# AS504XX_BreakoutV4.net
KiCad netlist of a schematic drawn in EAGLE
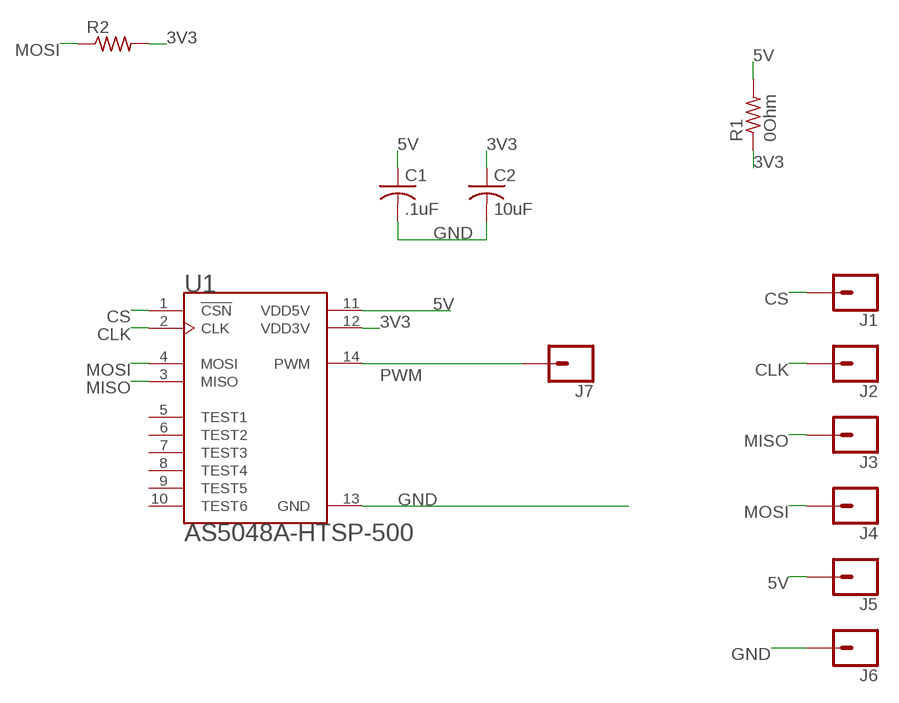
[diagram p0: schematic, sheet 1]

(export (version "E")
  (design (tool "Eeschema 10.0.6"))
  (components
    (comp (ref "C1")
      (value ".1uF")
      (footprint "eagle-import:C0402")
      (libsource (lib "eagle-import") (part "C-USC0402"))
    )
    (comp (ref "C2")
      (value "10uF")
      (footprint "eagle-import:C0402")
      (libsource (lib "eagle-import") (part "C-USC0402"))
    )
    (comp (ref "J1")
      (value "CONN_01")
      (footprint "eagle-import:1X01")
      (libsource (lib "eagle-import") (part "CONN_01"))
    )
    (comp (ref "J2")
      (value "CONN_01")
      (footprint "eagle-import:1X01")
      (libsource (lib "eagle-import") (part "CONN_01"))
    )
    (comp (ref "J3")
      (value "CONN_01")
      (footprint "eagle-import:1X01")
      (libsource (lib "eagle-import") (part "CONN_01"))
    )
    (comp (ref "J4")
      (value "CONN_01")
      (footprint "eagle-import:1X01")
      (libsource (lib "eagle-import") (part "CONN_01"))
    )
    (comp (ref "J5")
      (value "CONN_01")
      (footprint "eagle-import:1X01")
      (libsource (lib "eagle-import") (part "CONN_01"))
    )
    (comp (ref "J6")
      (value "CONN_01")
      (footprint "eagle-import:1X01")
      (libsource (lib "eagle-import") (part "CONN_01"))
    )
    (comp (ref "J7")
      (value "CONN_01")
      (footprint "eagle-import:1X01")
      (libsource (lib "eagle-import") (part "CONN_01"))
    )
    (comp (ref "R1")
      (value "0Ohm")
      (footprint "eagle-import:R0402")
      (libsource (lib "eagle-import") (part "R-US_R0402"))
    )
    (comp (ref "R2")
      (value "R-US_R0603")
      (footprint "eagle-import:R0603")
      (libsource (lib "eagle-import") (part "rcl_334_R-US_R0603"))
    )
    (comp (ref "U1")
      (value "AS5048A-HTSP-500")
      (footprint "eagle-import:SOP65P640X120-14N")
      (fields (field (name "DIGI-KEY_PART_NUMBER") "AS5048A-HTSP-500CT-ND") (field (name "MF") "ams"))
      (libsource (lib "eagle-import") (part "AS5048A-HTSP-500"))
    )
  )
  (nets
    (net (code "1") (name "/3V3") (class "Default")
      (node (ref "C2") (pin "1") (pinfunction "1_1") (pintype "passive"))
      (node (ref "R1") (pin "1") (pinfunction "1_1") (pintype "passive"))
      (node (ref "R2") (pin "2") (pinfunction "2_2") (pintype "passive"))
      (node (ref "U1") (pin "12") (pinfunction "VDD3V_12") (pintype "power_in"))
    )
    (net (code "2") (name "/5V") (class "Default")
      (node (ref "C1") (pin "1") (pinfunction "1_1") (pintype "passive"))
      (node (ref "J5") (pin "1") (pinfunction "1_1") (pintype "passive"))
      (node (ref "R1") (pin "2") (pinfunction "2_2") (pintype "passive"))
      (node (ref "U1") (pin "11") (pinfunction "VDD5V_11") (pintype "power_in"))
    )
    (net (code "3") (name "/CLK") (class "Default")
      (node (ref "J2") (pin "1") (pinfunction "1_1") (pintype "passive"))
      (node (ref "U1") (pin "2") (pinfunction "CLK_2") (pintype "input"))
    )
    (net (code "4") (name "/CS") (class "Default")
      (node (ref "J1") (pin "1") (pinfunction "1_1") (pintype "passive"))
      (node (ref "U1") (pin "1") (pinfunction "~{CSN}_1") (pintype "input"))
    )
    (net (code "5") (name "/GND") (class "Default")
      (node (ref "C1") (pin "2") (pinfunction "2_2") (pintype "passive"))
      (node (ref "C2") (pin "2") (pinfunction "2_2") (pintype "passive"))
      (node (ref "J6") (pin "1") (pinfunction "1_1") (pintype "passive"))
      (node (ref "U1") (pin "13") (pinfunction "GND_13") (pintype "passive"))
    )
    (net (code "6") (name "/MISO") (class "Default")
      (node (ref "J3") (pin "1") (pinfunction "1_1") (pintype "passive"))
      (node (ref "U1") (pin "3") (pinfunction "MISO_3") (pintype "bidirectional"))
    )
    (net (code "7") (name "/MOSI") (class "Default")
      (node (ref "J4") (pin "1") (pinfunction "1_1") (pintype "passive"))
      (node (ref "R2") (pin "1") (pinfunction "1_1") (pintype "passive"))
      (node (ref "U1") (pin "4") (pinfunction "MOSI_4") (pintype "input"))
    )
    (net (code "8") (name "/PWM") (class "Default")
      (node (ref "J7") (pin "1") (pinfunction "1_1") (pintype "passive"))
      (node (ref "U1") (pin "14") (pinfunction "PWM_14") (pintype "output"))
    )
    (net (code "9") (name "unconnected-(U1-TEST1-Pad5)") (class "Default")
      (node (ref "U1") (pin "5") (pinfunction "TEST1_5") (pintype "bidirectional"))
    )
    (net (code "10") (name "unconnected-(U1-TEST2-Pad6)") (class "Default")
      (node (ref "U1") (pin "6") (pinfunction "TEST2_6") (pintype "bidirectional"))
    )
    (net (code "11") (name "unconnected-(U1-TEST3-Pad7)") (class "Default")
      (node (ref "U1") (pin "7") (pinfunction "TEST3_7") (pintype "bidirectional"))
    )
    (net (code "12") (name "unconnected-(U1-TEST4-Pad8)") (class "Default")
      (node (ref "U1") (pin "8") (pinfunction "TEST4_8") (pintype "bidirectional"))
    )
    (net (code "13") (name "unconnected-(U1-TEST5-Pad9)") (class "Default")
      (node (ref "U1") (pin "9") (pinfunction "TEST5_9") (pintype "bidirectional"))
    )
    (net (code "14") (name "unconnected-(U1-TEST6-Pad10)") (class "Default")
      (node (ref "U1") (pin "10") (pinfunction "TEST6_10") (pintype "bidirectional"))
    )
  )
)
